# Communication.net
KiCad netlist of a schematic drawn in Altium Designer
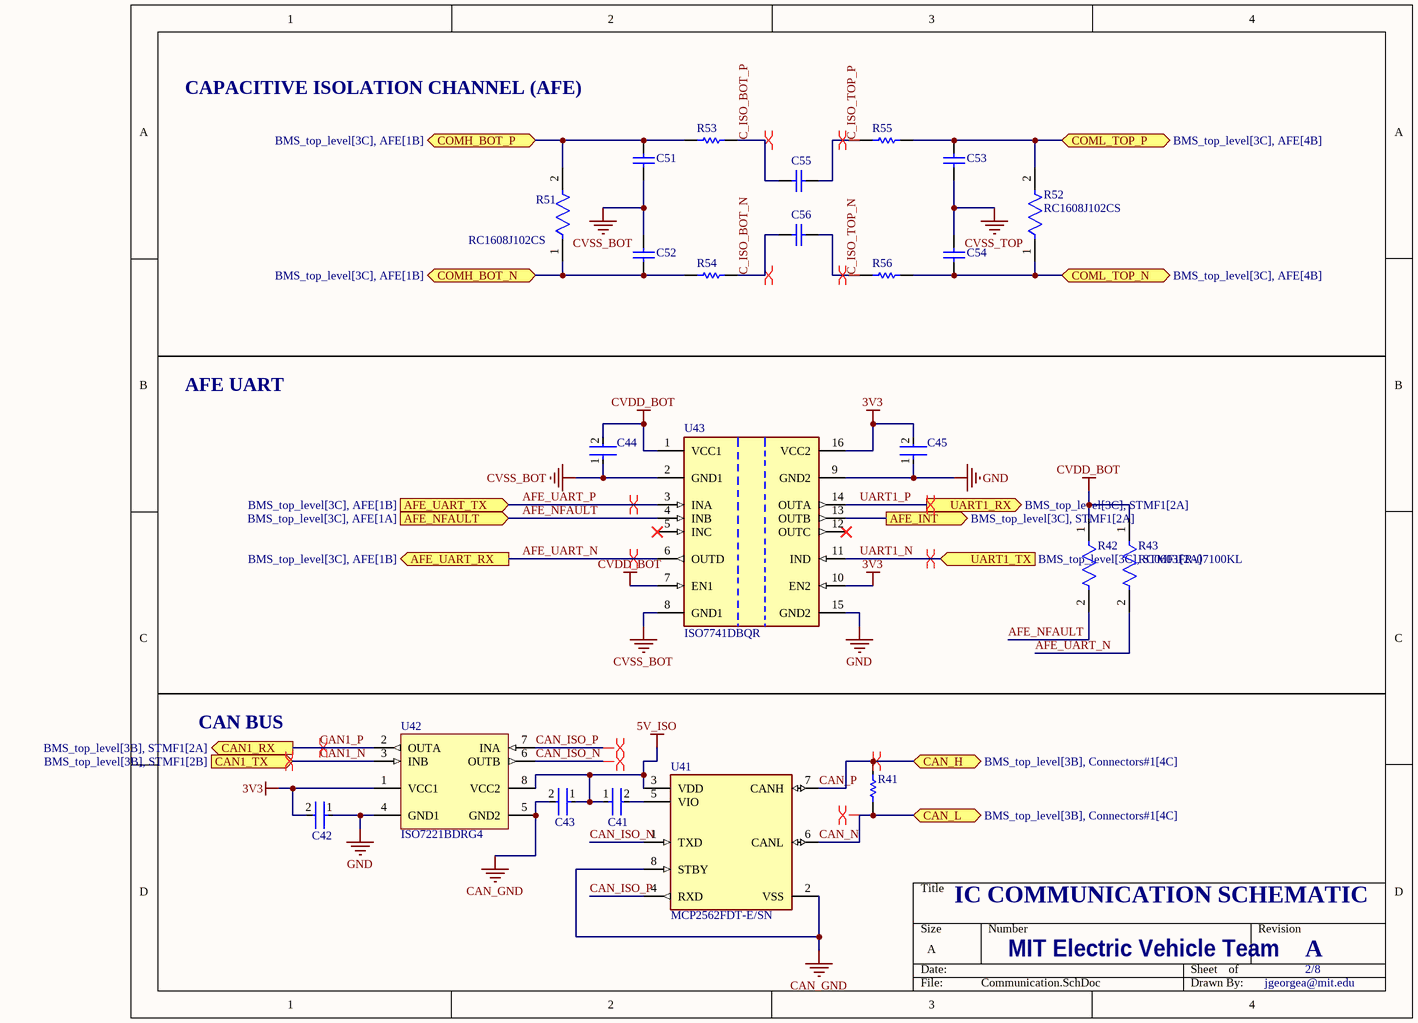
[diagram p0: Communication.SchDoc]

(export (version "E")
  (design (tool "Eeschema 10.0.6"))
  (components
    (comp (ref "C41")
      (value "CGA3E2X7R1H104K080AA")
      (footprint "FP-CGA3E-0_3-0_1-IPC_A")
      (description "Cap Ceramic 100nF 50V X7R 10% Pad SMD 0603 +125°C Automotive T/R")
      (fields (field (name "TOLERANCE") "10%") (field (name "VOLTAGE") "50V"))
      (libsource (lib "Altium Content Vault") (part "b4654b650e69147ec39a6b967a45e02"))
    )
    (comp (ref "C42")
      (value "CGA3E2X7R1H104K080AA")
      (footprint "FP-CGA3E-0_3-0_1-IPC_A")
      (description "Cap Ceramic 100nF 50V X7R 10% Pad SMD 0603 +125°C Automotive T/R")
      (fields (field (name "TOLERANCE") "10%") (field (name "VOLTAGE") "50V"))
      (libsource (lib "Altium Content Vault") (part "b4654b650e69147ec39a6b967a45e02"))
    )
    (comp (ref "C43")
      (value "CGA3E2X7R1H104K080AA")
      (footprint "FP-CGA3E-0_3-0_1-IPC_A")
      (description "Cap Ceramic 100nF 50V X7R 10% Pad SMD 0603 +125°C Automotive T/R")
      (fields (field (name "TOLERANCE") "10%") (field (name "VOLTAGE") "50V"))
      (libsource (lib "Altium Content Vault") (part "b4654b650e69147ec39a6b967a45e02"))
    )
    (comp (ref "C44")
      (value "CGA3E2X7R1H104K080AA")
      (footprint "FP-CGA3E-0_3-0_1-IPC_A")
      (description "Cap Ceramic 100nF 50V X7R 10% Pad SMD 0603 +125°C Automotive T/R")
      (fields (field (name "TOLERANCE") "10%") (field (name "VOLTAGE") "50V"))
      (libsource (lib "Altium Content Vault") (part "b4654b650e69147ec39a6b967a45e02"))
    )
    (comp (ref "C45")
      (value "CGA3E2X7R1H104K080AA")
      (footprint "FP-CGA3E-0_3-0_1-IPC_A")
      (description "Cap Ceramic 100nF 50V X7R 10% Pad SMD 0603 +125°C Automotive T/R")
      (fields (field (name "TOLERANCE") "10%") (field (name "VOLTAGE") "50V"))
      (libsource (lib "Altium Content Vault") (part "b4654b650e69147ec39a6b967a45e02"))
    )
    (comp (ref "C51")
      (value "06031C221KAT2A")
      (footprint "CAPC1608X90X35ML15T15")
      (fields (field (name "MANUFACTURER") "AVX Interconnect / Elco"))
      (libsource (lib "Altium Content Vault") (part "CAP"))
    )
    (comp (ref "C52")
      (value "06031C221KAT2A")
      (footprint "CAPC1608X90X35ML15T15")
      (fields (field (name "MANUFACTURER") "AVX Interconnect / Elco"))
      (libsource (lib "Altium Content Vault") (part "CAP"))
    )
    (comp (ref "C53")
      (value "06031C221KAT2A")
      (footprint "CAPC1608X90X35ML15T15")
      (fields (field (name "MANUFACTURER") "AVX Interconnect / Elco"))
      (libsource (lib "Altium Content Vault") (part "CAP"))
    )
    (comp (ref "C54")
      (value "06031C221KAT2A")
      (footprint "CAPC1608X90X35ML15T15")
      (fields (field (name "MANUFACTURER") "AVX Interconnect / Elco"))
      (libsource (lib "Altium Content Vault") (part "CAP"))
    )
    (comp (ref "C55")
      (value "08051C222JAT2A")
      (footprint "CAPC2013X94X50LL20T25")
      (fields (field (name "MANUFACTURER") "AVX Interconnect / Elco"))
      (libsource (lib "Altium Content Vault") (part "CAP"))
    )
    (comp (ref "C56")
      (value "08051C222JAT2A")
      (footprint "CAPC2013X94X50LL20T25")
      (fields (field (name "MANUFACTURER") "AVX Interconnect / Elco"))
      (libsource (lib "Altium Content Vault") (part "CAP"))
    )
    (comp (ref "R41")
      (value "ERJ-3EKF1200V")
      (footprint "RESC1609X55X30ML15T15")
      (description "Chip Resistor, 120 Ohm, +/- 1%, 0.1 W, -55 to 155 degC, 0603 (1608 Metric), RoHS, Tape and Reel")
      (fields (field (name "TOLERANCE") "1%") (field (name "MANUFACTURER") "Panasonic"))
      (libsource (lib "Altium Content Vault") (part "RES-2"))
    )
    (comp (ref "R42")
      (value "RC0603FR-07100KL")
      (footprint "FP-RC0603-0_55-MFG")
      (description "RES SMD 100K OHM 1% 1/10W 0603")
      (fields (field (name "TOLERANCE") "1%"))
      (libsource (lib "Altium Content Vault") (part "1029c3af85768c4190bb7ad29bc67b5"))
    )
    (comp (ref "R43")
      (value "RC0603FR-07100KL")
      (footprint "FP-RC0603-0_55-MFG")
      (description "RES SMD 100K OHM 1% 1/10W 0603")
      (fields (field (name "TOLERANCE") "1%"))
      (libsource (lib "Altium Content Vault") (part "1029c3af85768c4190bb7ad29bc67b5"))
    )
    (comp (ref "R51")
      (value "RC1608J102CS")
      (footprint "FP-RC1608-IPC_A")
      (description "Res Thick Film 0603 1kΩ 5% 0.1W ±100ppm/°C Molded SMD T/R")
      (fields (field (name "TOLERANCE") "5%"))
      (libsource (lib "Altium Content Vault") (part "1029c3af85768c4190bb7ad29bc67b5"))
    )
    (comp (ref "R52")
      (value "RC1608J102CS")
      (footprint "FP-RC1608-IPC_A")
      (description "Res Thick Film 0603 1kΩ 5% 0.1W ±100ppm/°C Molded SMD T/R")
      (fields (field (name "TOLERANCE") "5%"))
      (libsource (lib "Altium Content Vault") (part "1029c3af85768c4190bb7ad29bc67b5"))
    )
    (comp (ref "R53")
      (value "48R7 1% 0603(1608)")
      (footprint "RESC0603(1608)_M")
      (description "48R7 0.1W 1% 0603 (1608 Metric)  SMD")
      (fields (field (name "POWER") "0.1 W") (field (name "TOLERANCE") "1 %"))
      (libsource (lib "Altium Content Vault") (part "RES"))
    )
    (comp (ref "R54")
      (value "48R7 1% 0603(1608)")
      (footprint "RESC0603(1608)_M")
      (description "48R7 0.1W 1% 0603 (1608 Metric)  SMD")
      (fields (field (name "POWER") "0.1 W") (field (name "TOLERANCE") "1 %"))
      (libsource (lib "Altium Content Vault") (part "RES"))
    )
    (comp (ref "R55")
      (value "48R7 1% 0603(1608)")
      (footprint "RESC0603(1608)_M")
      (description "48R7 0.1W 1% 0603 (1608 Metric)  SMD")
      (fields (field (name "POWER") "0.1 W") (field (name "TOLERANCE") "1 %"))
      (libsource (lib "Altium Content Vault") (part "RES"))
    )
    (comp (ref "R56")
      (value "48R7 1% 0603(1608)")
      (footprint "RESC0603(1608)_M")
      (description "48R7 0.1W 1% 0603 (1608 Metric)  SMD")
      (fields (field (name "POWER") "0.1 W") (field (name "TOLERANCE") "1 %"))
      (libsource (lib "Altium Content Vault") (part "RES"))
    )
    (comp (ref "U41")
      (value "MCP2562FDT-E/SN")
      (footprint "FP-C04-057-SN-MFG")
      (description "IC TRANSCEIVER 1/1 8SOIC")
      (libsource (lib "Altium Content Vault") (part "fcb6c66e4429206983adab9201371df"))
    )
    (comp (ref "U42")
      (value "ISO7221BDRG4")
      (footprint "D0008B_M")
      (fields (field (name "MANUFACTURER") "Texas Instruments"))
      (libsource (lib "Altium Content Vault") (part "TI-ISO7221B-SOIC_D-8"))
    )
    (comp (ref "U43")
      (value "ISO7741DBQR")
      (footprint "FP-DBQ0016A-MFG")
      (fields
        (field (name "OCTOPART") "https://octopart.com/iso7741dbqr-texas+instruments-82338409")
        (field (name "MANUFACTURER") "Texas Instruments")
      )
      (libsource (lib "Altium Content Vault") (part "86c140552bb4d025f9381be7c20e1d5"))
    )
  )
  (nets
    (net (code "1") (name "/AFE_INT") (class "Default")
      (node (ref "U43") (pin "13") (pinfunction "OUTB_13") (pintype "output"))
    )
    (net (code "2") (name "/AFE_NFAULT") (class "Default")
      (node (ref "R42") (pin "2") (pinfunction "2_2") (pintype "passive"))
      (node (ref "U43") (pin "4") (pinfunction "INB_4") (pintype "input"))
    )
    (net (code "3") (name "/AFE_UART_N") (class "Default")
      (node (ref "R43") (pin "2") (pinfunction "2_2") (pintype "passive"))
      (node (ref "U43") (pin "6") (pinfunction "OUTD_6") (pintype "output"))
    )
    (net (code "4") (name "/AFE_UART_P") (class "Default")
      (node (ref "U43") (pin "3") (pinfunction "INA_3") (pintype "input"))
    )
    (net (code "5") (name "/CAN1_N") (class "Default")
      (node (ref "U42") (pin "3") (pinfunction "INB_3") (pintype "input"))
    )
    (net (code "6") (name "/CAN1_P") (class "Default")
      (node (ref "U42") (pin "2") (pinfunction "OUTA_2") (pintype "output"))
    )
    (net (code "7") (name "/CAN_ISO_N") (class "Default")
      (node (ref "U41") (pin "1") (pinfunction "TXD_1") (pintype "input"))
      (node (ref "U42") (pin "6") (pinfunction "OUTB_6") (pintype "output"))
    )
    (net (code "8") (name "/CAN_ISO_P") (class "Default")
      (node (ref "U41") (pin "4") (pinfunction "RXD_4") (pintype "output"))
      (node (ref "U42") (pin "7") (pinfunction "INA_7") (pintype "input"))
    )
    (net (code "9") (name "/CAN_N") (class "Default")
      (node (ref "R41") (pin "1") (pinfunction "1_1") (pintype "passive"))
      (node (ref "U41") (pin "6") (pinfunction "CANL_6") (pintype "bidirectional"))
    )
    (net (code "10") (name "/CAN_P") (class "Default")
      (node (ref "R41") (pin "2") (pinfunction "2_2") (pintype "passive"))
      (node (ref "U41") (pin "7") (pinfunction "CANH_7") (pintype "bidirectional"))
    )
    (net (code "11") (name "/COMH_BOT_N") (class "Default")
      (node (ref "C52") (pin "2") (pinfunction "2_2") (pintype "passive"))
      (node (ref "R51") (pin "1") (pinfunction "1_1") (pintype "passive"))
      (node (ref "R54") (pin "1") (pinfunction "1_1") (pintype "passive"))
    )
    (net (code "12") (name "/COMH_BOT_P") (class "Default")
      (node (ref "C51") (pin "2") (pinfunction "2_2") (pintype "passive"))
      (node (ref "R51") (pin "2") (pinfunction "2_2") (pintype "passive"))
      (node (ref "R53") (pin "1") (pinfunction "1_1") (pintype "passive"))
    )
    (net (code "13") (name "/COML_TOP_N") (class "Default")
      (node (ref "C54") (pin "2") (pinfunction "2_2") (pintype "passive"))
      (node (ref "R52") (pin "1") (pinfunction "1_1") (pintype "passive"))
      (node (ref "R56") (pin "2") (pinfunction "2_2") (pintype "passive"))
    )
    (net (code "14") (name "/COML_TOP_P") (class "Default")
      (node (ref "C53") (pin "2") (pinfunction "2_2") (pintype "passive"))
      (node (ref "R52") (pin "2") (pinfunction "2_2") (pintype "passive"))
      (node (ref "R55") (pin "2") (pinfunction "2_2") (pintype "passive"))
    )
    (net (code "15") (name "/C_ISO_BOT_N") (class "Default")
      (node (ref "C56") (pin "1") (pinfunction "1_1") (pintype "passive"))
      (node (ref "R54") (pin "2") (pinfunction "2_2") (pintype "passive"))
    )
    (net (code "16") (name "/C_ISO_BOT_P") (class "Default")
      (node (ref "C55") (pin "1") (pinfunction "1_1") (pintype "passive"))
      (node (ref "R53") (pin "2") (pinfunction "2_2") (pintype "passive"))
    )
    (net (code "17") (name "/C_ISO_TOP_N") (class "Default")
      (node (ref "C56") (pin "2") (pinfunction "2_2") (pintype "passive"))
      (node (ref "R56") (pin "1") (pinfunction "1_1") (pintype "passive"))
    )
    (net (code "18") (name "/C_ISO_TOP_P") (class "Default")
      (node (ref "C55") (pin "2") (pinfunction "2_2") (pintype "passive"))
      (node (ref "R55") (pin "1") (pinfunction "1_1") (pintype "passive"))
    )
    (net (code "19") (name "/UART1_N") (class "Default")
      (node (ref "U43") (pin "11") (pinfunction "IND_11") (pintype "input"))
    )
    (net (code "20") (name "/UART1_P") (class "Default")
      (node (ref "U43") (pin "14") (pinfunction "OUTA_14") (pintype "output"))
    )
    (net (code "21") (name "3V3") (class "Default")
      (node (ref "C42") (pin "2") (pinfunction "2_2") (pintype "passive"))
      (node (ref "C45") (pin "2") (pinfunction "2_2") (pintype "passive"))
      (node (ref "U42") (pin "1") (pinfunction "VCC1_1") (pintype "power_in"))
      (node (ref "U43") (pin "10") (pinfunction "EN2_10") (pintype "input"))
      (node (ref "U43") (pin "16") (pinfunction "VCC2_16") (pintype "power_in"))
    )
    (net (code "22") (name "5V_ISO") (class "Default")
      (node (ref "C41") (pin "1") (pinfunction "1_1") (pintype "passive"))
      (node (ref "C43") (pin "1") (pinfunction "1_1") (pintype "passive"))
      (node (ref "U41") (pin "3") (pinfunction "VDD_3") (pintype "power_in"))
      (node (ref "U42") (pin "8") (pinfunction "VCC2_8") (pintype "power_in"))
    )
    (net (code "23") (name "CAN_GND") (class "Default")
      (node (ref "C43") (pin "2") (pinfunction "2_2") (pintype "passive"))
      (node (ref "U41") (pin "2") (pinfunction "VSS_2") (pintype "power_in"))
      (node (ref "U41") (pin "8") (pinfunction "STBY_8") (pintype "input"))
      (node (ref "U42") (pin "5") (pinfunction "GND2_5") (pintype "power_in"))
    )
    (net (code "24") (name "CVDD_BOT") (class "Default")
      (node (ref "C44") (pin "2") (pinfunction "2_2") (pintype "passive"))
      (node (ref "R42") (pin "1") (pinfunction "1_1") (pintype "passive"))
      (node (ref "R43") (pin "1") (pinfunction "1_1") (pintype "passive"))
      (node (ref "U43") (pin "1") (pinfunction "VCC1_1") (pintype "power_in"))
      (node (ref "U43") (pin "7") (pinfunction "EN1_7") (pintype "input"))
    )
    (net (code "25") (name "CVSS_BOT") (class "Default")
      (node (ref "C44") (pin "1") (pinfunction "1_1") (pintype "passive"))
      (node (ref "C51") (pin "1") (pinfunction "1_1") (pintype "passive"))
      (node (ref "C52") (pin "1") (pinfunction "1_1") (pintype "passive"))
      (node (ref "U43") (pin "2") (pinfunction "GND1_2") (pintype "power_in"))
      (node (ref "U43") (pin "8") (pinfunction "GND1_8") (pintype "power_in"))
    )
    (net (code "26") (name "CVSS_TOP") (class "Default")
      (node (ref "C53") (pin "1") (pinfunction "1_1") (pintype "passive"))
      (node (ref "C54") (pin "1") (pinfunction "1_1") (pintype "passive"))
    )
    (net (code "27") (name "GND") (class "Default")
      (node (ref "C42") (pin "1") (pinfunction "1_1") (pintype "passive"))
      (node (ref "C45") (pin "1") (pinfunction "1_1") (pintype "passive"))
      (node (ref "U42") (pin "4") (pinfunction "GND1_4") (pintype "power_in"))
      (node (ref "U43") (pin "15") (pinfunction "GND2_15") (pintype "power_in"))
      (node (ref "U43") (pin "9") (pinfunction "GND2_9") (pintype "power_in"))
    )
    (net (code "28") (name "Net-(U41-VIO)") (class "Default")
      (node (ref "C41") (pin "2") (pinfunction "2_2") (pintype "passive"))
      (node (ref "U41") (pin "5") (pinfunction "VIO_5") (pintype "power_in"))
    )
    (net (code "29") (name "unconnected-(U43-INC-Pad5)") (class "Default")
      (node (ref "U43") (pin "5") (pinfunction "INC_5") (pintype "input+no_connect"))
    )
    (net (code "30") (name "unconnected-(U43-OUTC-Pad12)") (class "Default")
      (node (ref "U43") (pin "12") (pinfunction "OUTC_12") (pintype "output+no_connect"))
    )
  )
)
